# ProPrj_optical-usb-serial-port-module_20.net
KiCad netlist of a schematic drawn in EasyEDA Pro
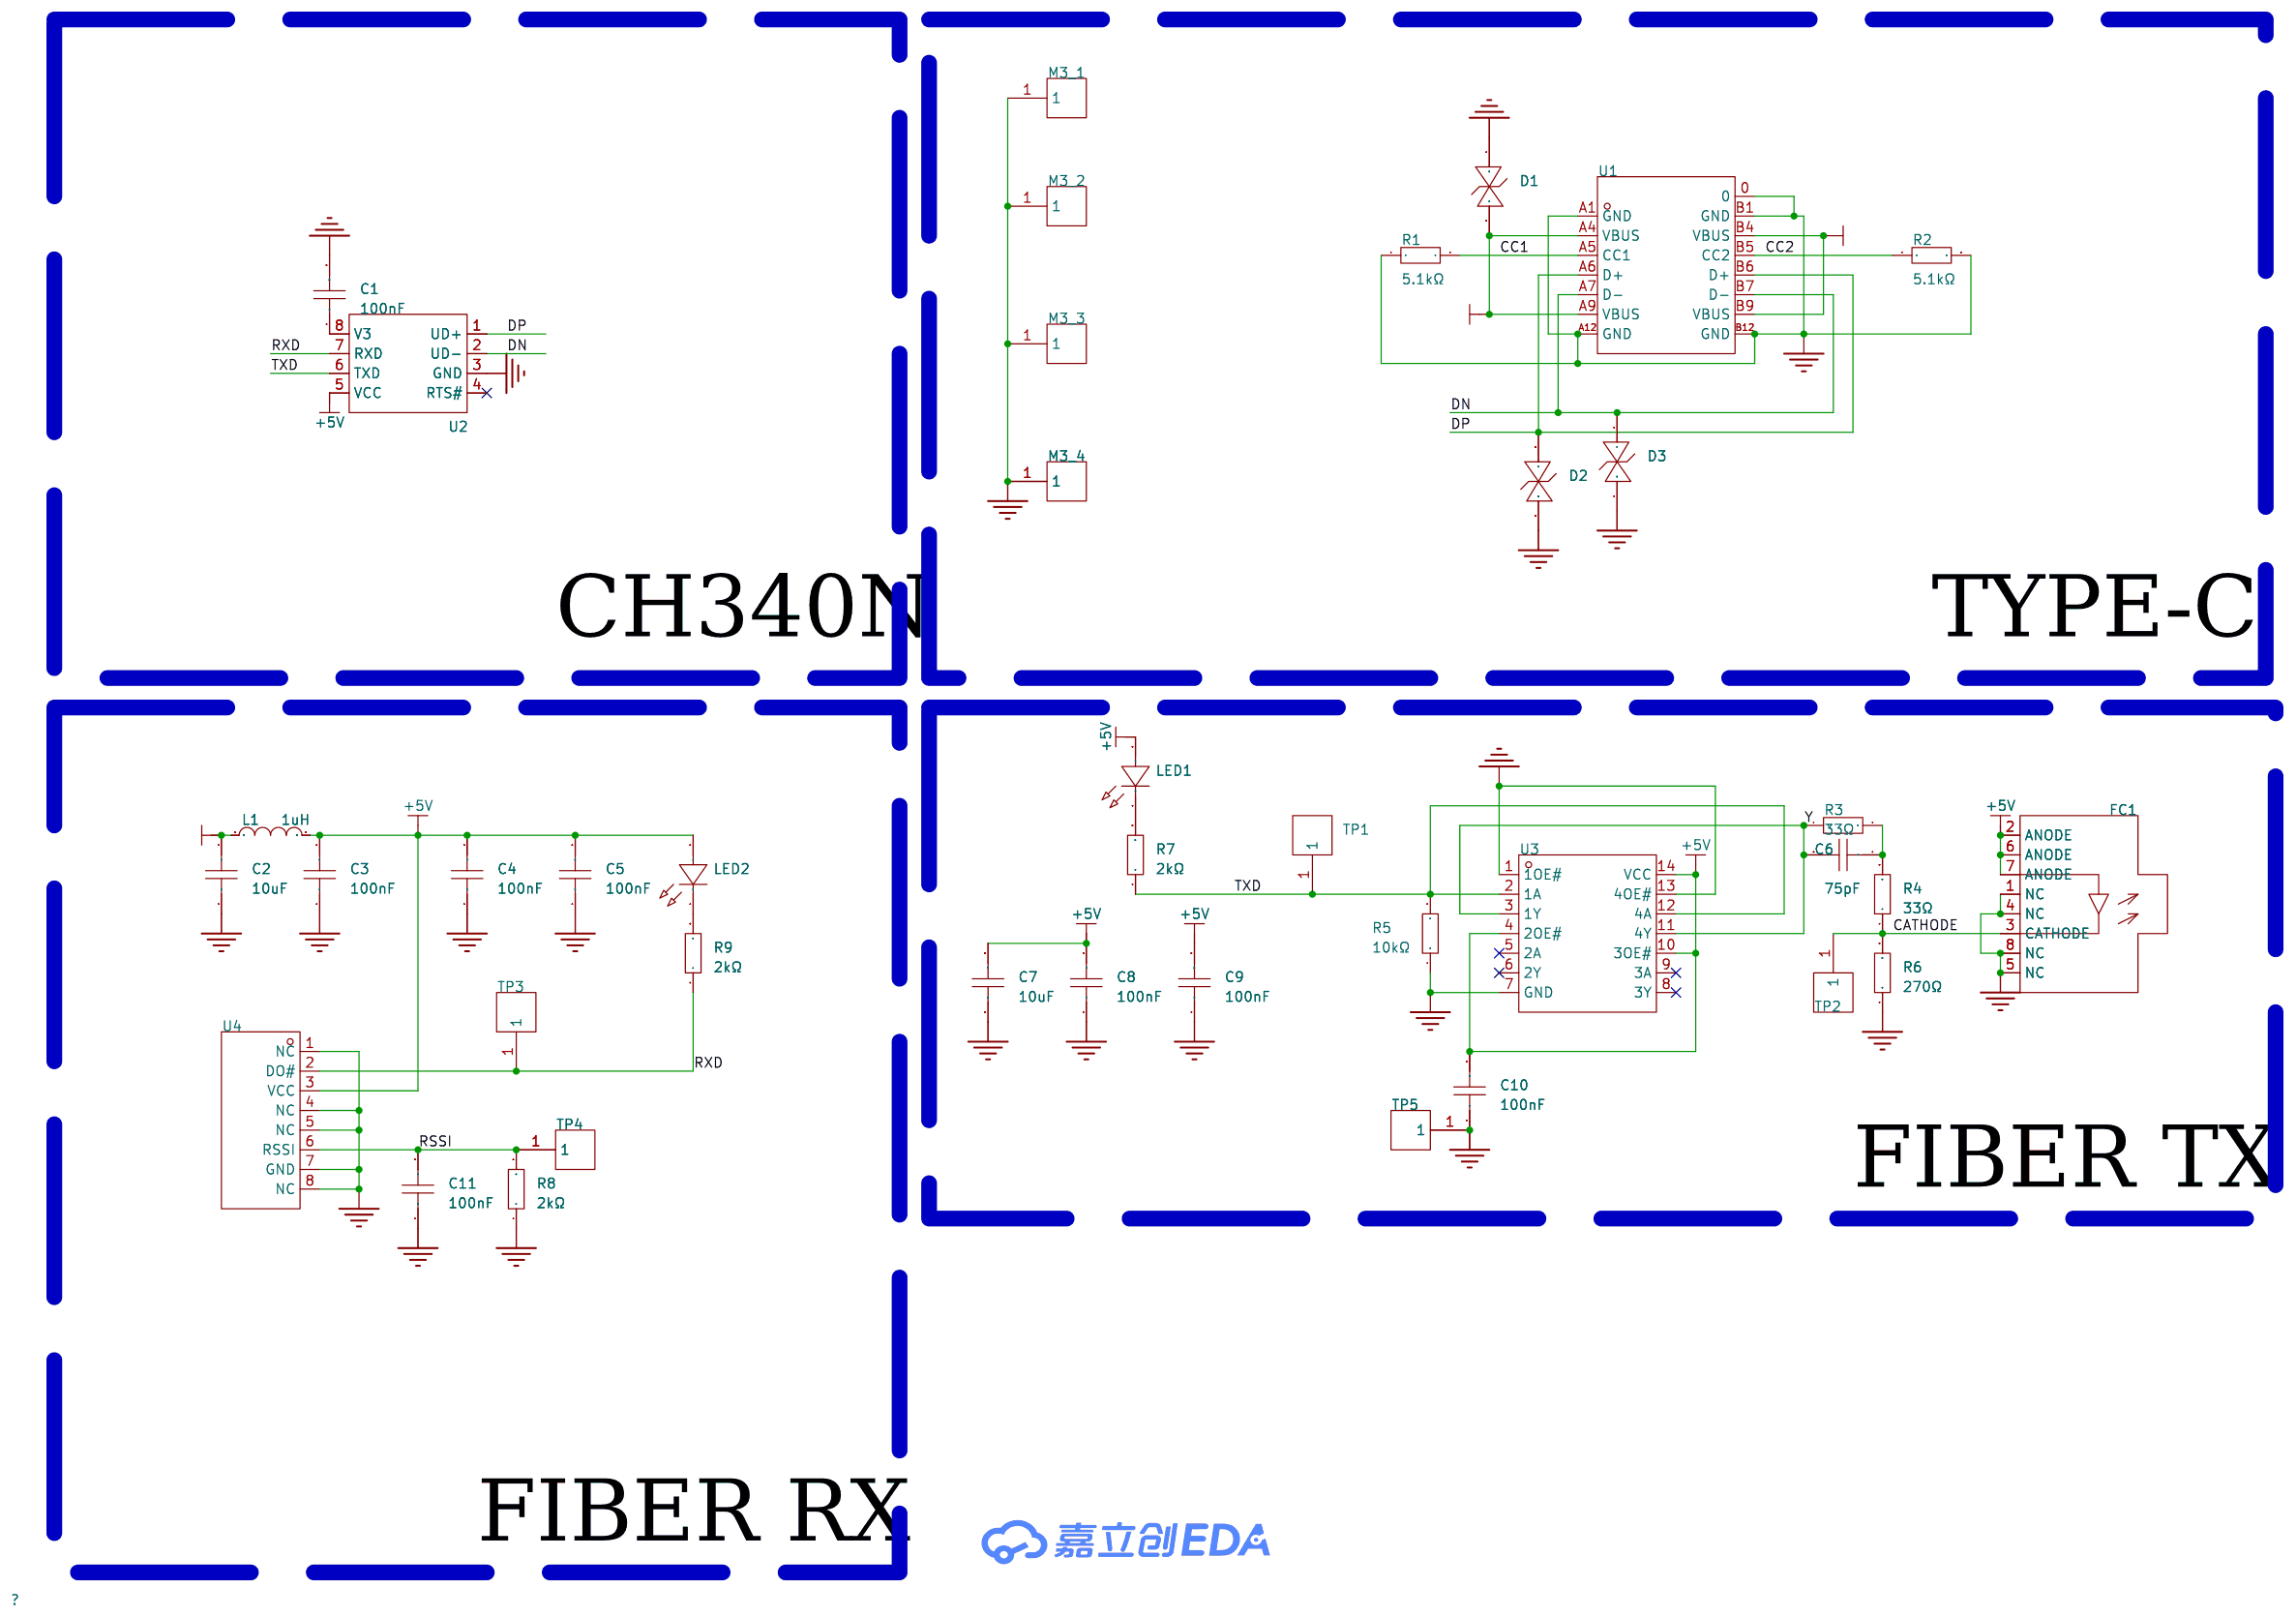
[diagram p0: schematic sheet]

(export (version "E")
  (design (tool "Eeschema 10.0.6"))
  (components
    (comp (ref "C1")
      (value "100nF")
      (footprint "easyedapro:C0603")
      (description "容值:100nF;精度:±10%;额定电压:50V;材质(温度系数):X7R;")
      (fields
        (field (name "Manufacturer Part") "CGA0603X7R104K500JT")
        (field (name "Manufacturer") "HRE(芯声)")
      )
      (libsource (lib "easyedapro") (part "CGA0603X7R104K500JT"))
    )
    (comp (ref "C2")
      (value "10uF")
      (footprint "easyedapro:C0603")
      (description "容值:10uF;精度:±10%;额定电压:10V;材质(温度系数):X5R;")
      (fields
        (field (name "Manufacturer Part") "CGA0603X5R106K100JT")
        (field (name "Manufacturer") "HRE(芯声)")
      )
      (libsource (lib "easyedapro") (part "CGA0603X5R106K100JT"))
    )
    (comp (ref "C3")
      (value "100nF")
      (footprint "easyedapro:C0603")
      (description "容值:100nF;精度:±10%;额定电压:50V;材质(温度系数):X7R;")
      (fields
        (field (name "Manufacturer Part") "CGA0603X7R104K500JT")
        (field (name "Manufacturer") "HRE(芯声)")
      )
      (libsource (lib "easyedapro") (part "CGA0603X7R104K500JT"))
    )
    (comp (ref "C4")
      (value "100nF")
      (footprint "easyedapro:C0603")
      (description "容值:100nF;精度:±10%;额定电压:50V;材质(温度系数):X7R;")
      (fields
        (field (name "Manufacturer Part") "CGA0603X7R104K500JT")
        (field (name "Manufacturer") "HRE(芯声)")
      )
      (libsource (lib "easyedapro") (part "CGA0603X7R104K500JT"))
    )
    (comp (ref "C5")
      (value "100nF")
      (footprint "easyedapro:C0603")
      (description "容值:100nF;精度:±10%;额定电压:50V;材质(温度系数):X7R;")
      (fields
        (field (name "Manufacturer Part") "CGA0603X7R104K500JT")
        (field (name "Manufacturer") "HRE(芯声)")
      )
      (libsource (lib "easyedapro") (part "CGA0603X7R104K500JT"))
    )
    (comp (ref "C6")
      (value "75pF")
      (footprint "easyedapro:C0603")
      (description "容值:75pF;精度:±5%;额定电压:50V;材质(温度系数):NP0;")
      (fields
        (field (name "Manufacturer Part") "CC0603JRNPO9BN750")
        (field (name "Manufacturer") "YAGEO(国巨)")
      )
      (libsource (lib "easyedapro") (part "CC0603JRNPO9BN750"))
    )
    (comp (ref "C7")
      (value "10uF")
      (footprint "easyedapro:C0603")
      (description "容值:10uF;精度:±10%;额定电压:10V;材质(温度系数):X5R;")
      (fields
        (field (name "Manufacturer Part") "CGA0603X5R106K100JT")
        (field (name "Manufacturer") "HRE(芯声)")
      )
      (libsource (lib "easyedapro") (part "CGA0603X5R106K100JT"))
    )
    (comp (ref "C8")
      (value "100nF")
      (footprint "easyedapro:C0603")
      (description "容值:100nF;精度:±10%;额定电压:50V;材质(温度系数):X7R;")
      (fields
        (field (name "Manufacturer Part") "CGA0603X7R104K500JT")
        (field (name "Manufacturer") "HRE(芯声)")
      )
      (libsource (lib "easyedapro") (part "CGA0603X7R104K500JT"))
    )
    (comp (ref "C9")
      (value "100nF")
      (footprint "easyedapro:C0603")
      (description "容值:100nF;精度:±10%;额定电压:50V;材质(温度系数):X7R;")
      (fields
        (field (name "Manufacturer Part") "CGA0603X7R104K500JT")
        (field (name "Manufacturer") "HRE(芯声)")
      )
      (libsource (lib "easyedapro") (part "CGA0603X7R104K500JT"))
    )
    (comp (ref "C10")
      (value "100nF")
      (footprint "easyedapro:C0603")
      (description "容值:100nF;精度:±10%;额定电压:50V;材质(温度系数):X7R;")
      (fields
        (field (name "Manufacturer Part") "CGA0603X7R104K500JT")
        (field (name "Manufacturer") "HRE(芯声)")
      )
      (libsource (lib "easyedapro") (part "CGA0603X7R104K500JT"))
    )
    (comp (ref "C11")
      (value "100nF")
      (footprint "easyedapro:C0603")
      (description "容值:100nF;精度:±10%;额定电压:50V;材质(温度系数):X7R;")
      (fields
        (field (name "Manufacturer Part") "CGA0603X7R104K500JT")
        (field (name "Manufacturer") "HRE(芯声)")
      )
      (libsource (lib "easyedapro") (part "CGA0603X7R104K500JT"))
    )
    (comp (ref "D1")
      (value "H5VL10B")
      (footprint "easyedapro:SOD-882_L1.0-W0.6-BI")
      (description "极性:双向;反向截止电压(Vrwm):5V;最大钳位电压:10V;峰值脉冲电流(Ipp):5A;峰值脉冲功率(Ppp):50W;击穿电压:5.6V;")
      (fields (field (name "Manufacturer") "宏迦橙"))
      (libsource (lib "easyedapro") (part "H5VL10B"))
    )
    (comp (ref "D2")
      (value "H5VL10B")
      (footprint "easyedapro:SOD-882_L1.0-W0.6-BI")
      (description "极性:双向;反向截止电压(Vrwm):5V;最大钳位电压:10V;峰值脉冲电流(Ipp):5A;峰值脉冲功率(Ppp):50W;击穿电压:5.6V;")
      (fields (field (name "Manufacturer") "宏迦橙"))
      (libsource (lib "easyedapro") (part "H5VL10B"))
    )
    (comp (ref "D3")
      (value "H5VL10B")
      (footprint "easyedapro:SOD-882_L1.0-W0.6-BI")
      (description "极性:双向;反向截止电压(Vrwm):5V;最大钳位电压:10V;峰值脉冲电流(Ipp):5A;峰值脉冲功率(Ppp):50W;击穿电压:5.6V;")
      (fields (field (name "Manufacturer") "宏迦橙"))
      (libsource (lib "easyedapro") (part "H5VL10B"))
    )
    (comp (ref "FC1")
      (value "HFBR-1414Z")
      (footprint "easyedapro:COMM-TH_HFBR-1414TZ")
      (description "类型:光纤接收模块;")
      (fields (field (name "Manufacturer") "Broadcom/AVAGO(安华高)"))
      (libsource (lib "easyedapro") (part "HFBR-1414Z"))
    )
    (comp (ref "L1")
      (value "1uH")
      (footprint "easyedapro:L0805")
      (description "电感值:1uH;精度:±20%;额定电流:3.2A;饱和电流(Isat):3.2A;类型:一体成型电感;")
      (fields
        (field (name "Manufacturer Part") "FTC201208S1R0MBCD")
        (field (name "Manufacturer") "cjiang(长江微电)")
      )
      (libsource (lib "easyedapro") (part "FTC201208S1R0MBCD"))
    )
    (comp (ref "LED1")
      (value "XL-1608UGC-04")
      (footprint "easyedapro:LED0603-RD_GREEN")
      (fields (field (name "Manufacturer") "XINGLIGHT(成兴光)"))
      (libsource (lib "easyedapro") (part "XL-1608UGC-04"))
    )
    (comp (ref "LED2")
      (value "XL-1608UGC-04")
      (footprint "easyedapro:LED0603-RD_GREEN")
      (fields (field (name "Manufacturer") "XINGLIGHT(成兴光)"))
      (libsource (lib "easyedapro") (part "XL-1608UGC-04"))
    )
    (comp (ref "M3_1")
      (value "M3X5.5X8+4*1.5贴片螺母")
      (footprint "easyedapro:SMD_BD5.5-D3.9")
      (libsource (lib "easyedapro") (part "M3X5.5X8+4*1.5贴片螺母"))
    )
    (comp (ref "M3_2")
      (value "M3X5.5X8+4*1.5贴片螺母")
      (footprint "easyedapro:SMD_BD5.5-D3.9")
      (libsource (lib "easyedapro") (part "M3X5.5X8+4*1.5贴片螺母"))
    )
    (comp (ref "M3_3")
      (value "M3X5.5X8+4*1.5贴片螺母")
      (footprint "easyedapro:SMD_BD5.5-D3.9")
      (libsource (lib "easyedapro") (part "M3X5.5X8+4*1.5贴片螺母"))
    )
    (comp (ref "M3_4")
      (value "M3X5.5X8+4*1.5贴片螺母")
      (footprint "easyedapro:SMD_BD5.5-D3.9")
      (libsource (lib "easyedapro") (part "M3X5.5X8+4*1.5贴片螺母"))
    )
    (comp (ref "R1")
      (value "5.1kΩ")
      (footprint "easyedapro:R0603")
      (description "电阻类型:厚膜电阻;阻值:5.1kΩ;精度:±1%;功率:100mW;最大工作电压:75V;温度系数:±100ppm/°C;")
      (fields
        (field (name "Manufacturer Part") "0603WAF5101T5E")
        (field (name "Manufacturer") "UNI-ROYAL(厚声)")
      )
      (libsource (lib "easyedapro") (part "0603WAF5101T5E"))
    )
    (comp (ref "R2")
      (value "5.1kΩ")
      (footprint "easyedapro:R0603")
      (description "电阻类型:厚膜电阻;阻值:5.1kΩ;精度:±1%;功率:100mW;最大工作电压:75V;温度系数:±100ppm/°C;")
      (fields
        (field (name "Manufacturer Part") "0603WAF5101T5E")
        (field (name "Manufacturer") "UNI-ROYAL(厚声)")
      )
      (libsource (lib "easyedapro") (part "0603WAF5101T5E"))
    )
    (comp (ref "R3")
      (value "33Ω")
      (footprint "easyedapro:R0603")
      (description "电阻类型:厚膜电阻;阻值:33Ω;精度:±1%;功率:100mW;最大工作电压:75V;温度系数:±100ppm/°C;")
      (fields
        (field (name "Manufacturer Part") "0603WAF330JT5E")
        (field (name "Manufacturer") "UNI-ROYAL(厚声)")
      )
      (libsource (lib "easyedapro") (part "0603WAF330JT5E"))
    )
    (comp (ref "R4")
      (value "33Ω")
      (footprint "easyedapro:R0603")
      (description "电阻类型:厚膜电阻;阻值:33Ω;精度:±1%;功率:100mW;最大工作电压:75V;温度系数:±100ppm/°C;")
      (fields
        (field (name "Manufacturer Part") "0603WAF330JT5E")
        (field (name "Manufacturer") "UNI-ROYAL(厚声)")
      )
      (libsource (lib "easyedapro") (part "0603WAF330JT5E"))
    )
    (comp (ref "R5")
      (value "10kΩ")
      (footprint "easyedapro:R0603")
      (description "电阻类型:厚膜电阻;阻值:10kΩ;精度:±1%;功率:100mW;最大工作电压:75V;温度系数:±100ppm/°C;")
      (fields
        (field (name "Manufacturer Part") "0603WAF1002T5E")
        (field (name "Manufacturer") "UNI-ROYAL(厚声)")
      )
      (libsource (lib "easyedapro") (part "0603WAF1002T5E"))
    )
    (comp (ref "R6")
      (value "270Ω")
      (footprint "easyedapro:R0603")
      (description "电阻类型:厚膜电阻;阻值:270Ω;精度:±1%;功率:100mW;最大工作电压:75V;温度系数:±100ppm/°C;")
      (fields
        (field (name "Manufacturer Part") "0603WAF2700T5E")
        (field (name "Manufacturer") "UNI-ROYAL(厚声)")
      )
      (libsource (lib "easyedapro") (part "0603WAF2700T5E"))
    )
    (comp (ref "R7")
      (value "2kΩ")
      (footprint "easyedapro:R0603")
      (description "电阻类型:厚膜电阻;阻值:2kΩ;精度:±1%;功率:100mW;最大工作电压:75V;温度系数:±100ppm/°C;")
      (fields
        (field (name "Manufacturer Part") "0603WAF2001T5E")
        (field (name "Manufacturer") "UNI-ROYAL(厚声)")
      )
      (libsource (lib "easyedapro") (part "0603WAF2001T5E"))
    )
    (comp (ref "R8")
      (value "2kΩ")
      (footprint "easyedapro:R0603")
      (description "电阻类型:厚膜电阻;阻值:2kΩ;精度:±1%;功率:100mW;最大工作电压:75V;温度系数:±100ppm/°C;")
      (fields
        (field (name "Manufacturer Part") "0603WAF2001T5E")
        (field (name "Manufacturer") "UNI-ROYAL(厚声)")
      )
      (libsource (lib "easyedapro") (part "0603WAF2001T5E"))
    )
    (comp (ref "R9")
      (value "2kΩ")
      (footprint "easyedapro:R0603")
      (description "电阻类型:厚膜电阻;阻值:2kΩ;精度:±1%;功率:100mW;最大工作电压:75V;温度系数:±100ppm/°C;")
      (fields
        (field (name "Manufacturer Part") "0603WAF2001T5E")
        (field (name "Manufacturer") "UNI-ROYAL(厚声)")
      )
      (libsource (lib "easyedapro") (part "0603WAF2001T5E"))
    )
    (comp (ref "TP1")
      (value "RH-5000")
      (footprint "easyedapro:TEST-TH_BD2.54-P1.4_RED")
      (fields (field (name "Manufacturer") "荣和"))
      (libsource (lib "easyedapro") (part "RH-5000"))
    )
    (comp (ref "TP2")
      (value "RH-5000")
      (footprint "easyedapro:TEST-TH_BD2.54-P1.4_RED")
      (fields (field (name "Manufacturer") "荣和"))
      (libsource (lib "easyedapro") (part "RH-5000"))
    )
    (comp (ref "TP3")
      (value "RH-5000")
      (footprint "easyedapro:TEST-TH_BD2.54-P1.4_RED")
      (fields (field (name "Manufacturer") "荣和"))
      (libsource (lib "easyedapro") (part "RH-5000"))
    )
    (comp (ref "TP4")
      (value "RH-5000")
      (footprint "easyedapro:TEST-TH_BD2.54-P1.4_RED")
      (fields (field (name "Manufacturer") "荣和"))
      (libsource (lib "easyedapro") (part "RH-5000"))
    )
    (comp (ref "TP5")
      (value "RH-5000")
      (footprint "easyedapro:TEST-TH_BD2.54-P1.4_RED")
      (fields (field (name "Manufacturer") "荣和"))
      (libsource (lib "easyedapro") (part "RH-5000"))
    )
    (comp (ref "U1")
      (value "TYPE-C 14PLC-H10.0")
      (footprint "easyedapro:USB-C-TH_SHOUHAN_TYPE-C-14PLC-H10.0")
      (fields (field (name "Manufacturer") "SHOU HAN(首韩)"))
      (libsource (lib "easyedapro") (part "TYPE-C 14PLC-H10.0"))
    )
    (comp (ref "U2")
      (value "CH340N")
      (footprint "easyedapro:SOP-8_L4.9-W3.9-P1.27-LS6.0-BL")
      (description "应用功能:USB转串口;接口协议:USB 2.0;通道数:1;数据速率:2Mbps;")
      (fields (field (name "Manufacturer") "WCH(南京沁恒)"))
      (libsource (lib "easyedapro") (part "CH340N_C2977777"))
    )
    (comp (ref "U3")
      (value "SN74ABT125DR")
      (footprint "easyedapro:SOIC-14_L8.7-W3.9-P1.27-LS6.0-BL")
      (description "输入类型:-;电源电压:4.5V~5.5V;元件数:4;每个元件位数:1;灌电流(IOL):64mA;拉电流(IOH):32mA;")
      (fields (field (name "Manufacturer") "TI(德州仪器)"))
      (libsource (lib "easyedapro") (part "SN74ABT125DR"))
    )
    (comp (ref "U4")
      (value "AFBR-2418TZ")
      (footprint "easyedapro:OPTO-TH_AVAGO_AFBR-2418TZ")
      (description "类型:光纤接收器;")
      (fields (field (name "Manufacturer") "Broadcom/AVAGO(安华高)"))
      (libsource (lib "easyedapro") (part "AFBR-2418TZ"))
    )
  )
  (nets
    (net (code "1") (name "+5V") (class "Default")
      (node (ref "C10") (pin "2") (pinfunction "2_2") (pintype "unspecified"))
      (node (ref "C3") (pin "2") (pinfunction "2_2") (pintype "unspecified"))
      (node (ref "C4") (pin "2") (pinfunction "2_2") (pintype "unspecified"))
      (node (ref "C5") (pin "2") (pinfunction "2_2") (pintype "unspecified"))
      (node (ref "C7") (pin "2") (pinfunction "2_2") (pintype "unspecified"))
      (node (ref "C8") (pin "2") (pinfunction "2_2") (pintype "unspecified"))
      (node (ref "C9") (pin "2") (pinfunction "2_2") (pintype "unspecified"))
      (node (ref "FC1") (pin "2") (pinfunction "ANODE_2") (pintype "unspecified"))
      (node (ref "FC1") (pin "6") (pinfunction "ANODE_6") (pintype "unspecified"))
      (node (ref "FC1") (pin "7") (pinfunction "ANODE_7") (pintype "unspecified"))
      (node (ref "L1") (pin "2") (pinfunction "2_2") (pintype "unspecified"))
      (node (ref "LED1") (pin "2") (pinfunction "A_2") (pintype "unspecified"))
      (node (ref "LED2") (pin "2") (pinfunction "A_2") (pintype "unspecified"))
      (node (ref "U2") (pin "5") (pinfunction "VCC_5") (pintype "unspecified"))
      (node (ref "U3") (pin "10") (pinfunction "3OE#_10") (pintype "unspecified"))
      (node (ref "U3") (pin "14") (pinfunction "VCC_14") (pintype "unspecified"))
      (node (ref "U3") (pin "4") (pinfunction "2OE#_4") (pintype "unspecified"))
      (node (ref "U4") (pin "3") (pinfunction "VCC_3") (pintype "unspecified"))
    )
    (net (code "2") (name "/CATHODE") (class "Default")
      (node (ref "FC1") (pin "3") (pinfunction "CATHODE_3") (pintype "unspecified"))
      (node (ref "R4") (pin "1") (pinfunction "1_1") (pintype "input"))
      (node (ref "R6") (pin "2") (pinfunction "2_2") (pintype "input"))
      (node (ref "TP2") (pin "1") (pinfunction "1_1") (pintype "unspecified"))
    )
    (net (code "3") (name "/CC1") (class "Default")
      (node (ref "R1") (pin "2") (pinfunction "2_2") (pintype "input"))
      (node (ref "U1") (pin "A5") (pinfunction "CC1_A5") (pintype "unspecified"))
    )
    (net (code "4") (name "/CC2") (class "Default")
      (node (ref "R2") (pin "1") (pinfunction "1_1") (pintype "input"))
      (node (ref "U1") (pin "B5") (pinfunction "CC2_B5") (pintype "unspecified"))
    )
    (net (code "5") (name "/DN") (class "Default")
      (node (ref "D3") (pin "2") (pinfunction "A_2") (pintype "unspecified"))
      (node (ref "U1") (pin "A7") (pinfunction "D-_A7") (pintype "unspecified"))
      (node (ref "U1") (pin "B7") (pinfunction "D-_B7") (pintype "unspecified"))
      (node (ref "U2") (pin "2") (pinfunction "UD-_2") (pintype "unspecified"))
    )
    (net (code "6") (name "/DP") (class "Default")
      (node (ref "D2") (pin "2") (pinfunction "A_2") (pintype "unspecified"))
      (node (ref "U1") (pin "A6") (pinfunction "D+_A6") (pintype "unspecified"))
      (node (ref "U1") (pin "B6") (pinfunction "D+_B6") (pintype "unspecified"))
      (node (ref "U2") (pin "1") (pinfunction "UD+_1") (pintype "unspecified"))
    )
    (net (code "7") (name "/RSSI") (class "Default")
      (node (ref "C11") (pin "2") (pinfunction "2_2") (pintype "unspecified"))
      (node (ref "R8") (pin "2") (pinfunction "2_2") (pintype "input"))
      (node (ref "TP4") (pin "1") (pinfunction "1_1") (pintype "unspecified"))
      (node (ref "U4") (pin "6") (pinfunction "RSSI_6") (pintype "unspecified"))
    )
    (net (code "8") (name "/RXD") (class "Default")
      (node (ref "R9") (pin "1") (pinfunction "1_1") (pintype "input"))
      (node (ref "TP3") (pin "1") (pinfunction "1_1") (pintype "unspecified"))
      (node (ref "U2") (pin "7") (pinfunction "RXD_7") (pintype "unspecified"))
      (node (ref "U4") (pin "2") (pinfunction "DO#_2") (pintype "unspecified"))
    )
    (net (code "9") (name "/TXD") (class "Default")
      (node (ref "R5") (pin "2") (pinfunction "2_2") (pintype "input"))
      (node (ref "R7") (pin "1") (pinfunction "1_1") (pintype "input"))
      (node (ref "TP1") (pin "1") (pinfunction "1_1") (pintype "unspecified"))
      (node (ref "U2") (pin "6") (pinfunction "TXD_6") (pintype "unspecified"))
      (node (ref "U3") (pin "12") (pinfunction "4A_12") (pintype "unspecified"))
      (node (ref "U3") (pin "2") (pinfunction "1A_2") (pintype "unspecified"))
    )
    (net (code "10") (name "/Y") (class "Default")
      (node (ref "C6") (pin "2") (pinfunction "2_2") (pintype "unspecified"))
      (node (ref "R3") (pin "1") (pinfunction "1_1") (pintype "input"))
      (node (ref "U3") (pin "11") (pinfunction "4Y_11") (pintype "unspecified"))
      (node (ref "U3") (pin "3") (pinfunction "1Y_3") (pintype "unspecified"))
    )
    (net (code "11") (name "GND") (class "Default")
      (node (ref "C1") (pin "2") (pinfunction "2_2") (pintype "unspecified"))
      (node (ref "C10") (pin "1") (pinfunction "1_1") (pintype "unspecified"))
      (node (ref "C11") (pin "1") (pinfunction "1_1") (pintype "unspecified"))
      (node (ref "C2") (pin "1") (pinfunction "1_1") (pintype "unspecified"))
      (node (ref "C3") (pin "1") (pinfunction "1_1") (pintype "unspecified"))
      (node (ref "C4") (pin "1") (pinfunction "1_1") (pintype "unspecified"))
      (node (ref "C5") (pin "1") (pinfunction "1_1") (pintype "unspecified"))
      (node (ref "C7") (pin "1") (pinfunction "1_1") (pintype "unspecified"))
      (node (ref "C8") (pin "1") (pinfunction "1_1") (pintype "unspecified"))
      (node (ref "C9") (pin "1") (pinfunction "1_1") (pintype "unspecified"))
      (node (ref "D1") (pin "1") (pinfunction "C_1") (pintype "unspecified"))
      (node (ref "D2") (pin "1") (pinfunction "C_1") (pintype "unspecified"))
      (node (ref "D3") (pin "1") (pinfunction "C_1") (pintype "unspecified"))
      (node (ref "FC1") (pin "1") (pinfunction "NC_1") (pintype "unspecified"))
      (node (ref "FC1") (pin "4") (pinfunction "NC_4") (pintype "unspecified"))
      (node (ref "FC1") (pin "5") (pinfunction "NC_5") (pintype "unspecified"))
      (node (ref "FC1") (pin "8") (pinfunction "NC_8") (pintype "unspecified"))
      (node (ref "M3_1") (pin "1") (pinfunction "1_1") (pintype "unspecified"))
      (node (ref "M3_2") (pin "1") (pinfunction "1_1") (pintype "unspecified"))
      (node (ref "M3_3") (pin "1") (pinfunction "1_1") (pintype "unspecified"))
      (node (ref "M3_4") (pin "1") (pinfunction "1_1") (pintype "unspecified"))
      (node (ref "R1") (pin "1") (pinfunction "1_1") (pintype "input"))
      (node (ref "R2") (pin "2") (pinfunction "2_2") (pintype "input"))
      (node (ref "R5") (pin "1") (pinfunction "1_1") (pintype "input"))
      (node (ref "R6") (pin "1") (pinfunction "1_1") (pintype "input"))
      (node (ref "R8") (pin "1") (pinfunction "1_1") (pintype "input"))
      (node (ref "TP5") (pin "1") (pinfunction "1_1") (pintype "unspecified"))
      (node (ref "U1") (pin "0") (pinfunction "0_0") (pintype "unspecified"))
      (node (ref "U1") (pin "A1") (pinfunction "GND_A1") (pintype "unspecified"))
      (node (ref "U1") (pin "A12") (pinfunction "GND_A12") (pintype "unspecified"))
      (node (ref "U1") (pin "B1") (pinfunction "GND_B1") (pintype "unspecified"))
      (node (ref "U1") (pin "B12") (pinfunction "GND_B12") (pintype "unspecified"))
      (node (ref "U2") (pin "3") (pinfunction "GND_3") (pintype "unspecified"))
      (node (ref "U3") (pin "1") (pinfunction "1OE#_1") (pintype "unspecified"))
      (node (ref "U3") (pin "13") (pinfunction "4OE#_13") (pintype "unspecified"))
      (node (ref "U3") (pin "7") (pinfunction "GND_7") (pintype "unspecified"))
      (node (ref "U4") (pin "1") (pinfunction "NC_1") (pintype "unspecified"))
      (node (ref "U4") (pin "4") (pinfunction "NC_4") (pintype "unspecified"))
      (node (ref "U4") (pin "5") (pinfunction "NC_5") (pintype "unspecified"))
      (node (ref "U4") (pin "7") (pinfunction "GND_7") (pintype "unspecified"))
      (node (ref "U4") (pin "8") (pinfunction "NC_8") (pintype "unspecified"))
    )
    (net (code "12") (name "Net-(C6-Pad1)") (class "Default")
      (node (ref "C6") (pin "1") (pinfunction "1_1") (pintype "unspecified"))
      (node (ref "R3") (pin "2") (pinfunction "2_2") (pintype "input"))
      (node (ref "R4") (pin "2") (pinfunction "2_2") (pintype "input"))
    )
    (net (code "13") (name "Net-(LED1-K)") (class "Default")
      (node (ref "LED1") (pin "1") (pinfunction "K_1") (pintype "unspecified"))
      (node (ref "R7") (pin "2") (pinfunction "2_2") (pintype "input"))
    )
    (net (code "14") (name "Net-(LED2-K)") (class "Default")
      (node (ref "LED2") (pin "1") (pinfunction "K_1") (pintype "unspecified"))
      (node (ref "R9") (pin "2") (pinfunction "2_2") (pintype "input"))
    )
    (net (code "15") (name "Net-(U2-V3)") (class "Default")
      (node (ref "C1") (pin "1") (pinfunction "1_1") (pintype "unspecified"))
      (node (ref "U2") (pin "8") (pinfunction "V3_8") (pintype "unspecified"))
    )
    (net (code "16") (name "VUSB") (class "Default")
      (node (ref "C2") (pin "2") (pinfunction "2_2") (pintype "unspecified"))
      (node (ref "D1") (pin "2") (pinfunction "A_2") (pintype "unspecified"))
      (node (ref "L1") (pin "1") (pinfunction "1_1") (pintype "unspecified"))
      (node (ref "U1") (pin "A4") (pinfunction "VBUS_A4") (pintype "unspecified"))
      (node (ref "U1") (pin "A9") (pinfunction "VBUS_A9") (pintype "unspecified"))
      (node (ref "U1") (pin "B4") (pinfunction "VBUS_B4") (pintype "unspecified"))
      (node (ref "U1") (pin "B9") (pinfunction "VBUS_B9") (pintype "unspecified"))
    )
    (net (code "17") (name "unconnected-(U2-RTS#-Pad4)") (class "Default")
      (node (ref "U2") (pin "4") (pinfunction "RTS#_4") (pintype "unspecified+no_connect"))
    )
    (net (code "18") (name "unconnected-(U3-2A-Pad5)") (class "Default")
      (node (ref "U3") (pin "5") (pinfunction "2A_5") (pintype "unspecified+no_connect"))
    )
    (net (code "19") (name "unconnected-(U3-2Y-Pad6)") (class "Default")
      (node (ref "U3") (pin "6") (pinfunction "2Y_6") (pintype "unspecified+no_connect"))
    )
    (net (code "20") (name "unconnected-(U3-3A-Pad9)") (class "Default")
      (node (ref "U3") (pin "9") (pinfunction "3A_9") (pintype "unspecified+no_connect"))
    )
    (net (code "21") (name "unconnected-(U3-3Y-Pad8)") (class "Default")
      (node (ref "U3") (pin "8") (pinfunction "3Y_8") (pintype "unspecified+no_connect"))
    )
  )
)
